# SparkFun_Energy_Harvester_Breakout-LTC35.net
KiCad netlist of a schematic drawn in EAGLE
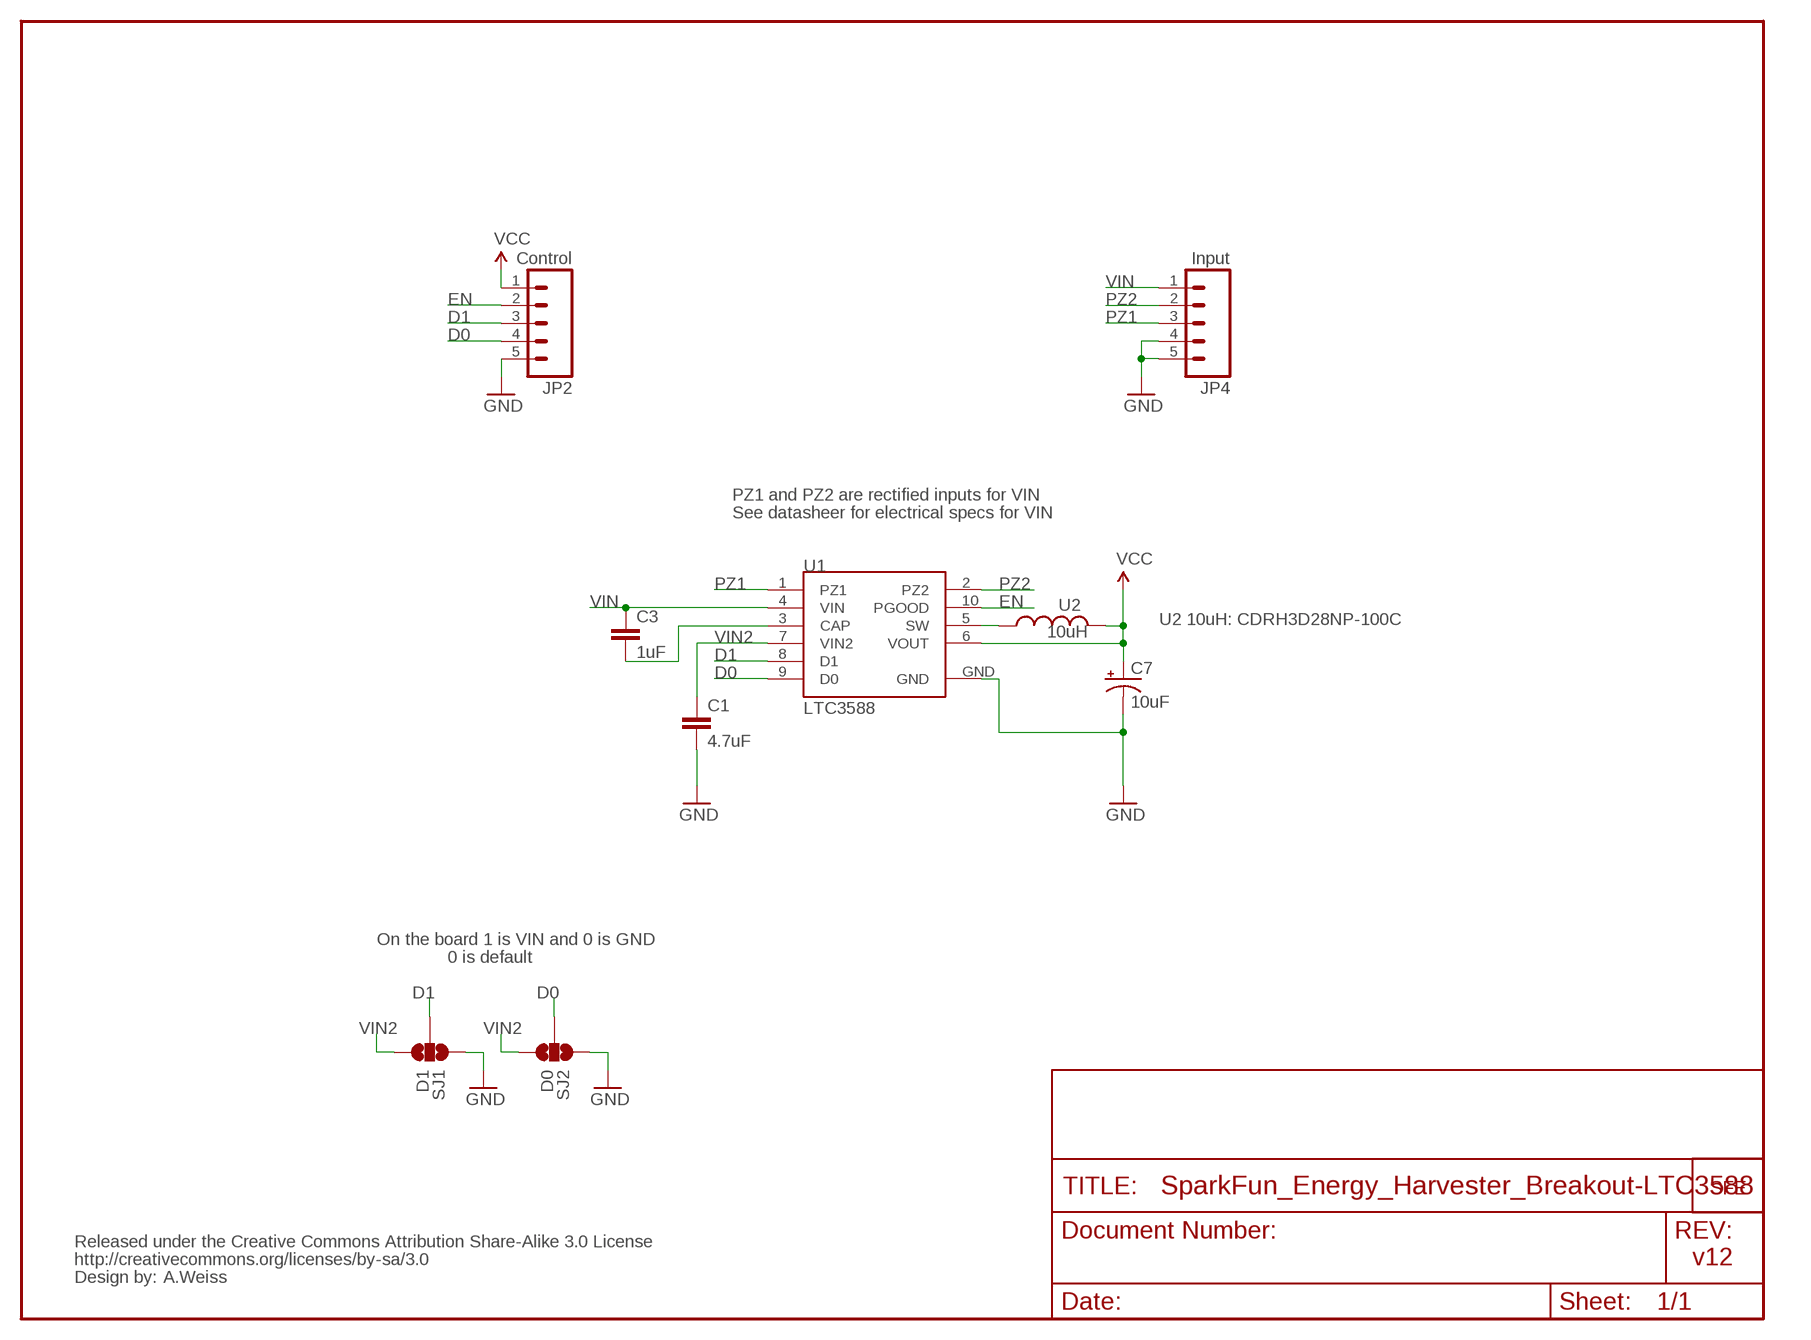
[diagram p0: schematic, sheet 1]

(export (version "E")
  (design (tool "Eeschema 10.0.6"))
  (components
    (comp (ref "C1")
      (value "4.7uF")
      (footprint "eagle-import:0402-CAP")
      (libsource (lib "eagle-import") (part "CAP0402-CAP"))
    )
    (comp (ref "C3")
      (value "1uF")
      (footprint "eagle-import:0402-CAP")
      (libsource (lib "eagle-import") (part "CAP0402-CAP"))
    )
    (comp (ref "C7")
      (value "10uF")
      (footprint "eagle-import:EIA3216")
      (libsource (lib "eagle-import") (part "CAP_POL1206"))
    )
    (comp (ref "JP1")
      (value "LOGO-SFESK")
      (footprint "eagle-import:SFE-LOGO-FLAME")
      (libsource (lib "eagle-import") (part "LOGO-SFESK"))
    )
    (comp (ref "JP2")
      (value "Control")
      (footprint "eagle-import:1X05")
      (libsource (lib "eagle-import") (part "M05PTH"))
    )
    (comp (ref "JP4")
      (value "Input")
      (footprint "eagle-import:1X05")
      (libsource (lib "eagle-import") (part "M05PTH"))
    )
    (comp (ref "SJ1")
      (value "D1")
      (footprint "eagle-import:SJ_3_PASTE2&3")
      (libsource (lib "eagle-import") (part "SOLDERJUMPER_2WAYPASTE2&3"))
    )
    (comp (ref "SJ2")
      (value "D0")
      (footprint "eagle-import:SJ_3_PASTE1&2")
      (libsource (lib "eagle-import") (part "SOLDERJUMPER_2WAYPASTE1&2"))
    )
    (comp (ref "U$1")
      (value "CREATIVE_COMMONS")
      (footprint "eagle-import:CREATIVE_COMMONS")
      (libsource (lib "eagle-import") (part "CREATIVE_COMMONS"))
    )
    (comp (ref "U1")
      (value "LTC3588")
      (footprint "eagle-import:MSOP-10-GNDPAD")
      (libsource (lib "eagle-import") (part "LTC3588_"))
    )
    (comp (ref "U2")
      (value "10uH")
      (footprint "eagle-import:CDRH3D28")
      (libsource (lib "eagle-import") (part "INDUCTOR-"))
    )
  )
  (nets
    (net (code "1") (name "/D0") (class "Default")
      (node (ref "JP2") (pin "4") (pinfunction "4_4") (pintype "passive"))
      (node (ref "SJ2") (pin "2") (pinfunction "2_2") (pintype "passive"))
      (node (ref "U1") (pin "9") (pinfunction "D0_9") (pintype "bidirectional"))
    )
    (net (code "2") (name "/D1") (class "Default")
      (node (ref "JP2") (pin "3") (pinfunction "3_3") (pintype "passive"))
      (node (ref "SJ1") (pin "2") (pinfunction "2_2") (pintype "passive"))
      (node (ref "U1") (pin "8") (pinfunction "D1_8") (pintype "bidirectional"))
    )
    (net (code "3") (name "/EN") (class "Default")
      (node (ref "JP2") (pin "2") (pinfunction "2_2") (pintype "passive"))
      (node (ref "U1") (pin "10") (pinfunction "PGOOD_10") (pintype "bidirectional"))
    )
    (net (code "4") (name "/PZ1") (class "Default")
      (node (ref "JP4") (pin "3") (pinfunction "3_3") (pintype "passive"))
      (node (ref "U1") (pin "1") (pinfunction "PZ1_1") (pintype "bidirectional"))
    )
    (net (code "5") (name "/PZ2") (class "Default")
      (node (ref "JP4") (pin "2") (pinfunction "2_2") (pintype "passive"))
      (node (ref "U1") (pin "2") (pinfunction "PZ2_2") (pintype "bidirectional"))
    )
    (net (code "6") (name "/VIN") (class "Default")
      (node (ref "C3") (pin "1") (pinfunction "1_1") (pintype "passive"))
      (node (ref "JP4") (pin "1") (pinfunction "1_1") (pintype "passive"))
      (node (ref "U1") (pin "4") (pinfunction "VIN_4") (pintype "bidirectional"))
    )
    (net (code "7") (name "/VIN2") (class "Default")
      (node (ref "C1") (pin "1") (pinfunction "1_1") (pintype "passive"))
      (node (ref "SJ1") (pin "3") (pinfunction "3_3") (pintype "passive"))
      (node (ref "SJ2") (pin "3") (pinfunction "3_3") (pintype "passive"))
      (node (ref "U1") (pin "7") (pinfunction "VIN2_7") (pintype "bidirectional"))
    )
    (net (code "8") (name "GND") (class "Default")
      (node (ref "C1") (pin "2") (pinfunction "2_2") (pintype "passive"))
      (node (ref "C7") (pin "C") (pinfunction "-_C") (pintype "passive"))
      (node (ref "JP2") (pin "5") (pinfunction "5_5") (pintype "passive"))
      (node (ref "JP4") (pin "4") (pinfunction "4_4") (pintype "passive"))
      (node (ref "JP4") (pin "5") (pinfunction "5_5") (pintype "passive"))
      (node (ref "SJ1") (pin "1") (pinfunction "1_1") (pintype "passive"))
      (node (ref "SJ2") (pin "1") (pinfunction "1_1") (pintype "passive"))
      (node (ref "U1") (pin "GND") (pinfunction "GND_GND") (pintype "bidirectional"))
    )
    (net (code "9") (name "Net-(U1-CAP)") (class "Default")
      (node (ref "C3") (pin "2") (pinfunction "2_2") (pintype "passive"))
      (node (ref "U1") (pin "3") (pinfunction "CAP_3") (pintype "bidirectional"))
    )
    (net (code "10") (name "Net-(U1-SW)") (class "Default")
      (node (ref "U1") (pin "5") (pinfunction "SW_5") (pintype "bidirectional"))
      (node (ref "U2") (pin "1") (pinfunction "1_1") (pintype "passive"))
    )
    (net (code "11") (name "VCC") (class "Default")
      (node (ref "C7") (pin "A") (pinfunction "+_A") (pintype "passive"))
      (node (ref "JP2") (pin "1") (pinfunction "1_1") (pintype "passive"))
      (node (ref "U1") (pin "6") (pinfunction "VOUT_6") (pintype "bidirectional"))
      (node (ref "U2") (pin "2") (pinfunction "2_2") (pintype "passive"))
    )
  )
)
